# mLRS-dualE28-board02-v010.net
KiCad netlist of a schematic drawn in EAGLE
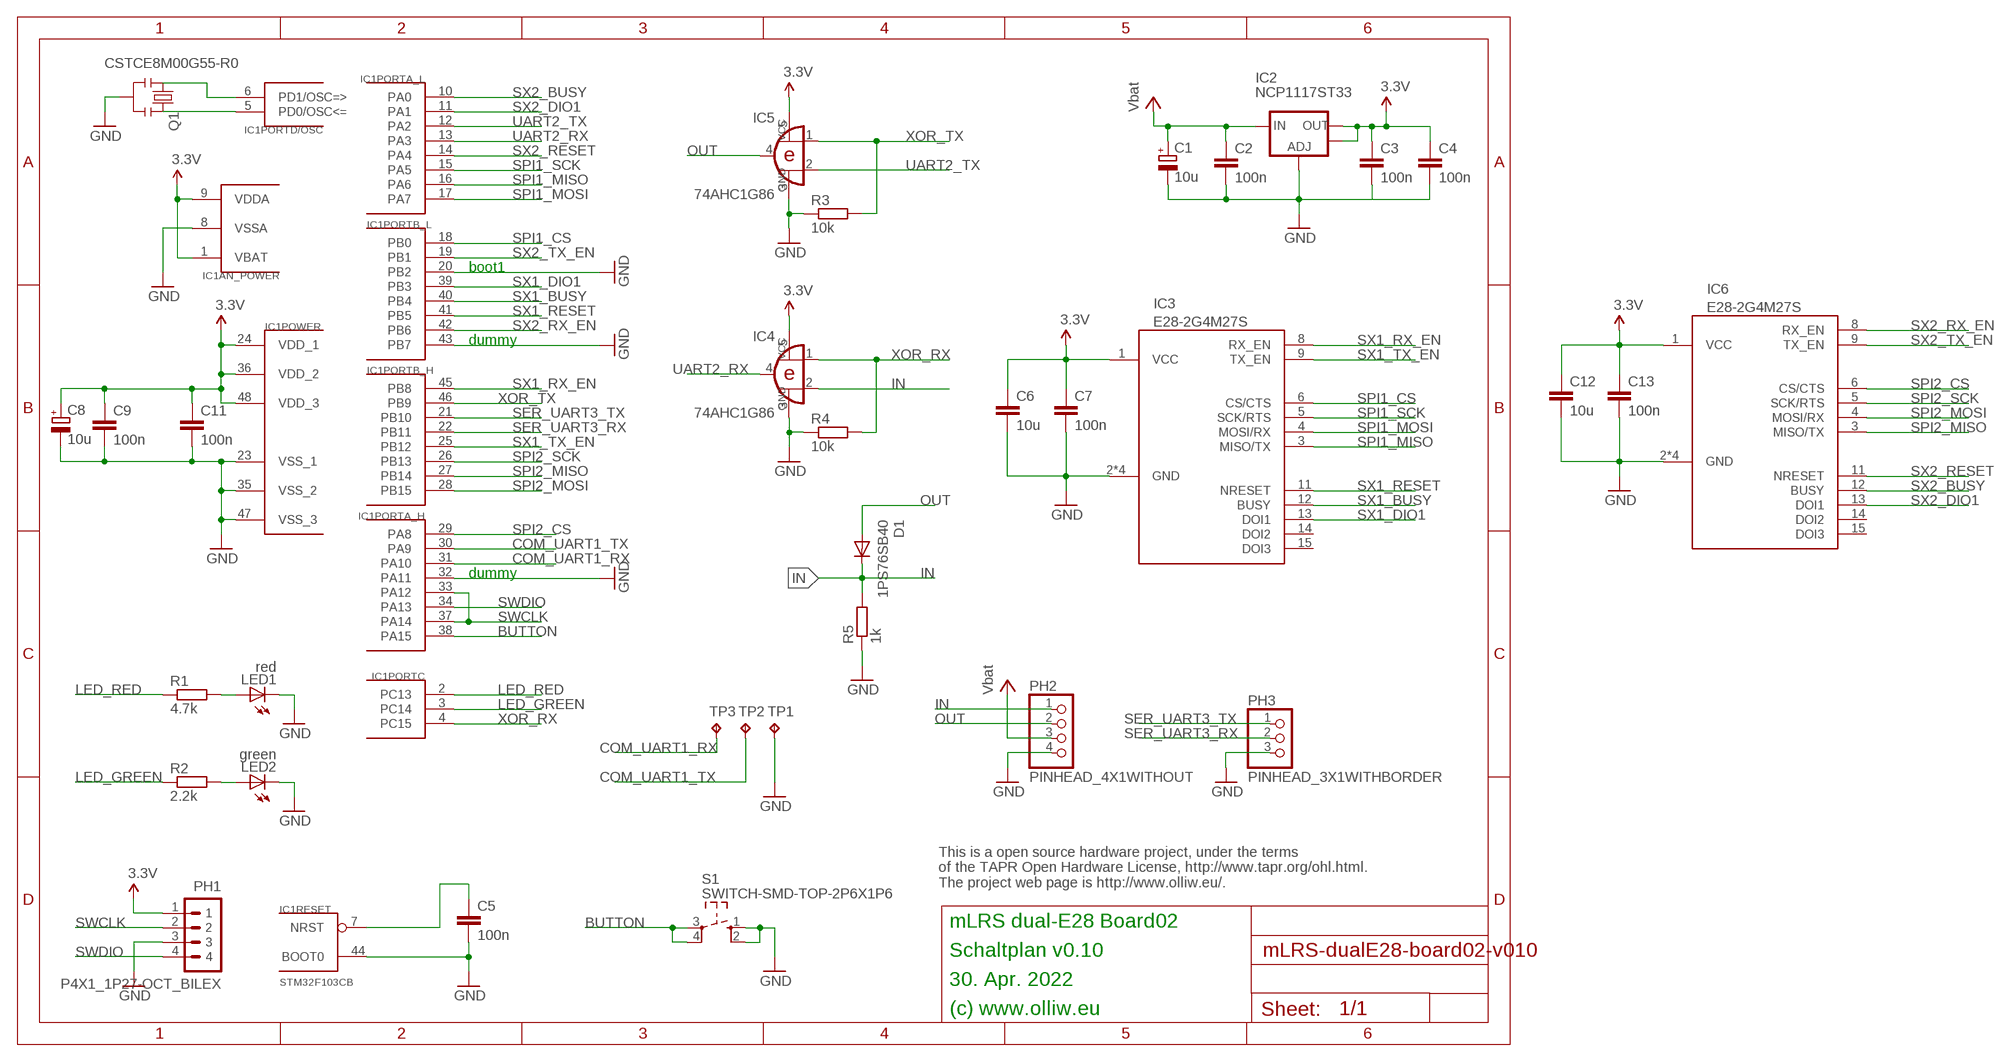
[diagram p0: schematic, sheet 1]

(export (version "E")
  (design (tool "Eeschema 10.0.6"))
  (components
    (comp (ref "C1")
      (value "10u")
      (footprint "eagle-import:SMC_A")
      (libsource (lib "eagle-import") (part "CPOL-EUSMCA"))
    )
    (comp (ref "C2")
      (value "100n")
      (footprint "eagle-import:C0603")
      (libsource (lib "eagle-import") (part "C-EUC0603"))
    )
    (comp (ref "C3")
      (value "100n")
      (footprint "eagle-import:C0402")
      (libsource (lib "eagle-import") (part "C-EUC0402"))
    )
    (comp (ref "C4")
      (value "100n")
      (footprint "eagle-import:C0402")
      (libsource (lib "eagle-import") (part "C-EUC0402"))
    )
    (comp (ref "C5")
      (value "100n")
      (footprint "eagle-import:C0402")
      (libsource (lib "eagle-import") (part "C-EUC0402"))
    )
    (comp (ref "C6")
      (value "10u")
      (footprint "eagle-import:C0603")
      (libsource (lib "eagle-import") (part "C-EUC0603"))
    )
    (comp (ref "C7")
      (value "100n")
      (footprint "eagle-import:C0402")
      (libsource (lib "eagle-import") (part "C-EUC0402"))
    )
    (comp (ref "C8")
      (value "10u")
      (footprint "eagle-import:SMC_A")
      (libsource (lib "eagle-import") (part "CPOL-EUSMCA"))
    )
    (comp (ref "C9")
      (value "100n")
      (footprint "eagle-import:C0402")
      (libsource (lib "eagle-import") (part "C-EUC0402"))
    )
    (comp (ref "C11")
      (value "100n")
      (footprint "eagle-import:C0402")
      (libsource (lib "eagle-import") (part "C-EUC0402"))
    )
    (comp (ref "C12")
      (value "10u")
      (footprint "eagle-import:C0603")
      (libsource (lib "eagle-import") (part "C-EUC0603"))
    )
    (comp (ref "C13")
      (value "100n")
      (footprint "eagle-import:C0402")
      (libsource (lib "eagle-import") (part "C-EUC0402"))
    )
    (comp (ref "D1")
      (value "1PS76SB40")
      (footprint "eagle-import:SOD110-R")
      (libsource (lib "eagle-import") (part "DIODE-SOD110-R"))
    )
    (comp (ref "IC1")
      (value "STM32F103CB")
      (footprint "eagle-import:TQFP48")
      (libsource (lib "eagle-import") (part "STM32F10XCXT6"))
    )
    (comp (ref "IC2")
      (value "NCP1117ST33")
      (footprint "eagle-import:SOT223")
      (libsource (lib "eagle-import") (part "V_REG_LM1117SOT223"))
    )
    (comp (ref "IC3")
      (value "E28-2G4M27S")
      (footprint "eagle-import:E28-2G4M27")
      (libsource (lib "eagle-import") (part "E28"))
    )
    (comp (ref "IC4")
      (value "74AHC1G86")
      (footprint "eagle-import:SOT23-5-VER1")
      (libsource (lib "eagle-import") (part "74AHC1G86"))
    )
    (comp (ref "IC5")
      (value "74AHC1G86")
      (footprint "eagle-import:SOT23-5-VER1")
      (libsource (lib "eagle-import") (part "74AHC1G86"))
    )
    (comp (ref "IC6")
      (value "E28-2G4M27S")
      (footprint "eagle-import:E28-2G4M27")
      (libsource (lib "eagle-import") (part "E28"))
    )
    (comp (ref "LED1")
      (value "red")
      (footprint "eagle-import:CHIPLED_0603")
      (libsource (lib "eagle-import") (part "LEDCHIPLED_0603"))
    )
    (comp (ref "LED2")
      (value "green")
      (footprint "eagle-import:CHIPLED_0603")
      (libsource (lib "eagle-import") (part "LEDCHIPLED_0603"))
    )
    (comp (ref "PH1")
      (value "P4X1_1P27-OCT_BILEX")
      (footprint "eagle-import:4X1_1P27_OCT_BILEX")
      (libsource (lib "eagle-import") (part "P4X1_1P27-OCT_BILEX"))
    )
    (comp (ref "PH2")
      (value "PINHEAD_4X1WITHOUT")
      (footprint "eagle-import:PINHEAD_4X1_WO")
      (libsource (lib "eagle-import") (part "PINHEAD_4X1WITHOUT"))
    )
    (comp (ref "PH3")
      (value "PINHEAD_3X1WITHBORDER")
      (footprint "eagle-import:PINHEAD_3X1")
      (libsource (lib "eagle-import") (part "PINHEAD_3X1WITHBORDER"))
    )
    (comp (ref "Q1")
      (value "CSTCE8M00G55-R0")
      (footprint "eagle-import:RESONATOR-SMD")
      (libsource (lib "eagle-import") (part "RESONATORSMD"))
    )
    (comp (ref "R1")
      (value "4.7k")
      (footprint "eagle-import:R0402")
      (libsource (lib "eagle-import") (part "R-EU_R0402"))
    )
    (comp (ref "R2")
      (value "2.2k")
      (footprint "eagle-import:R0402")
      (libsource (lib "eagle-import") (part "R-EU_R0402"))
    )
    (comp (ref "R3")
      (value "10k")
      (footprint "eagle-import:R0402")
      (libsource (lib "eagle-import") (part "R-EU_R0402"))
    )
    (comp (ref "R4")
      (value "10k")
      (footprint "eagle-import:R0402")
      (libsource (lib "eagle-import") (part "R-EU_R0402"))
    )
    (comp (ref "R5")
      (value "1k")
      (footprint "eagle-import:R0402")
      (libsource (lib "eagle-import") (part "R-EU_R0402"))
    )
    (comp (ref "S1")
      (value "SWITCH-SMD-TOP-2P6X1P6")
      (footprint "eagle-import:TACTILE-SWITCH-SMD-TOP-2P6X1X6")
      (libsource (lib "eagle-import") (part "SWITCH-SMD-TOP-2P6X1P6"))
    )
    (comp (ref "TP1")
      (value "TPB1,27")
      (footprint "eagle-import:B1,27")
      (libsource (lib "eagle-import") (part "TPB1,27"))
    )
    (comp (ref "TP2")
      (value "TPB1,27")
      (footprint "eagle-import:B1,27")
      (libsource (lib "eagle-import") (part "TPB1,27"))
    )
    (comp (ref "TP3")
      (value "TPB1,27")
      (footprint "eagle-import:B1,27")
      (libsource (lib "eagle-import") (part "TPB1,27"))
    )
  )
  (nets
    (net (code "1") (name "/BUTTON") (class "Default")
      (node (ref "IC1") (pin "38") (pinfunction "PA15_38") (pintype "bidirectional"))
      (node (ref "S1") (pin "3") (pinfunction "3_3") (pintype "passive"))
      (node (ref "S1") (pin "4") (pinfunction "4_4") (pintype "passive"))
    )
    (net (code "2") (name "/COM_UART1_RX") (class "Default")
      (node (ref "IC1") (pin "31") (pinfunction "PA10_31") (pintype "bidirectional"))
      (node (ref "TP3") (pin "TP") (pinfunction "TP_TP") (pintype "input"))
    )
    (net (code "3") (name "/COM_UART1_TX") (class "Default")
      (node (ref "IC1") (pin "30") (pinfunction "PA9_30") (pintype "bidirectional"))
      (node (ref "TP2") (pin "TP") (pinfunction "TP_TP") (pintype "input"))
    )
    (net (code "4") (name "/LED_GREEN") (class "Default")
      (node (ref "IC1") (pin "3") (pinfunction "PC14_3") (pintype "bidirectional"))
      (node (ref "R2") (pin "1") (pinfunction "1_1") (pintype "passive"))
    )
    (net (code "5") (name "/LED_RED") (class "Default")
      (node (ref "IC1") (pin "2") (pinfunction "PC13_2") (pintype "bidirectional"))
      (node (ref "R1") (pin "1") (pinfunction "1_1") (pintype "passive"))
    )
    (net (code "6") (name "/OUT") (class "Default")
      (node (ref "D1") (pin "A") (pinfunction "A_A") (pintype "passive"))
      (node (ref "IC5") (pin "4") (pinfunction "O_4") (pintype "output"))
      (node (ref "PH2") (pin "2") (pinfunction "2_2") (pintype "passive"))
    )
    (net (code "7") (name "/SER_UART3_RX") (class "Default")
      (node (ref "IC1") (pin "22") (pinfunction "PB11_22") (pintype "bidirectional"))
      (node (ref "PH3") (pin "2") (pinfunction "3_2") (pintype "passive"))
    )
    (net (code "8") (name "/SER_UART3_TX") (class "Default")
      (node (ref "IC1") (pin "21") (pinfunction "PB10_21") (pintype "bidirectional"))
      (node (ref "PH3") (pin "1") (pinfunction "1_1") (pintype "passive"))
    )
    (net (code "9") (name "/SPI1_CS") (class "Default")
      (node (ref "IC1") (pin "18") (pinfunction "PB0_18") (pintype "bidirectional"))
      (node (ref "IC3") (pin "6") (pinfunction "CS/CTS_6") (pintype "bidirectional"))
    )
    (net (code "10") (name "/SPI1_MISO") (class "Default")
      (node (ref "IC1") (pin "16") (pinfunction "PA6_16") (pintype "bidirectional"))
      (node (ref "IC3") (pin "3") (pinfunction "MISO/TX_3") (pintype "bidirectional"))
    )
    (net (code "11") (name "/SPI1_MOSI") (class "Default")
      (node (ref "IC1") (pin "17") (pinfunction "PA7_17") (pintype "bidirectional"))
      (node (ref "IC3") (pin "4") (pinfunction "MOSI/RX_4") (pintype "bidirectional"))
    )
    (net (code "12") (name "/SPI1_SCK") (class "Default")
      (node (ref "IC1") (pin "15") (pinfunction "PA5_15") (pintype "bidirectional"))
      (node (ref "IC3") (pin "5") (pinfunction "SCK/RTS_5") (pintype "bidirectional"))
    )
    (net (code "13") (name "/SPI2_CS") (class "Default")
      (node (ref "IC1") (pin "29") (pinfunction "PA8_29") (pintype "bidirectional"))
      (node (ref "IC6") (pin "6") (pinfunction "CS/CTS_6") (pintype "bidirectional"))
    )
    (net (code "14") (name "/SPI2_MISO") (class "Default")
      (node (ref "IC1") (pin "27") (pinfunction "PB14_27") (pintype "bidirectional"))
      (node (ref "IC6") (pin "3") (pinfunction "MISO/TX_3") (pintype "bidirectional"))
    )
    (net (code "15") (name "/SPI2_MOSI") (class "Default")
      (node (ref "IC1") (pin "28") (pinfunction "PB15_28") (pintype "bidirectional"))
      (node (ref "IC6") (pin "4") (pinfunction "MOSI/RX_4") (pintype "bidirectional"))
    )
    (net (code "16") (name "/SPI2_SCK") (class "Default")
      (node (ref "IC1") (pin "26") (pinfunction "PB13_26") (pintype "bidirectional"))
      (node (ref "IC6") (pin "5") (pinfunction "SCK/RTS_5") (pintype "bidirectional"))
    )
    (net (code "17") (name "/SWCLK") (class "Default")
      (node (ref "IC1") (pin "33") (pinfunction "PA12_33") (pintype "bidirectional"))
      (node (ref "IC1") (pin "37") (pinfunction "PA14_37") (pintype "bidirectional"))
      (node (ref "PH1") (pin "2") (pinfunction "2_2") (pintype "passive"))
    )
    (net (code "18") (name "/SWDIO") (class "Default")
      (node (ref "IC1") (pin "34") (pinfunction "PA13_34") (pintype "bidirectional"))
      (node (ref "PH1") (pin "4") (pinfunction "4_4") (pintype "passive"))
    )
    (net (code "19") (name "/SX1_BUSY") (class "Default")
      (node (ref "IC1") (pin "40") (pinfunction "PB4_40") (pintype "bidirectional"))
      (node (ref "IC3") (pin "12") (pinfunction "BUSY_12") (pintype "bidirectional"))
    )
    (net (code "20") (name "/SX1_DIO1") (class "Default")
      (node (ref "IC1") (pin "39") (pinfunction "PB3_39") (pintype "bidirectional"))
      (node (ref "IC3") (pin "13") (pinfunction "DOI1_13") (pintype "bidirectional"))
    )
    (net (code "21") (name "/SX1_RESET") (class "Default")
      (node (ref "IC1") (pin "41") (pinfunction "PB5_41") (pintype "bidirectional"))
      (node (ref "IC3") (pin "11") (pinfunction "NRESET_11") (pintype "input"))
    )
    (net (code "22") (name "/SX1_RX_EN") (class "Default")
      (node (ref "IC1") (pin "45") (pinfunction "PB8_45") (pintype "bidirectional"))
      (node (ref "IC3") (pin "8") (pinfunction "RX_EN_8") (pintype "bidirectional"))
    )
    (net (code "23") (name "/SX1_TX_EN") (class "Default")
      (node (ref "IC1") (pin "25") (pinfunction "PB12_25") (pintype "bidirectional"))
      (node (ref "IC3") (pin "9") (pinfunction "TX_EN_9") (pintype "bidirectional"))
    )
    (net (code "24") (name "/SX2_BUSY") (class "Default")
      (node (ref "IC1") (pin "10") (pinfunction "PA0_10") (pintype "bidirectional"))
      (node (ref "IC6") (pin "12") (pinfunction "BUSY_12") (pintype "bidirectional"))
    )
    (net (code "25") (name "/SX2_DIO1") (class "Default")
      (node (ref "IC1") (pin "11") (pinfunction "PA1_11") (pintype "bidirectional"))
      (node (ref "IC6") (pin "13") (pinfunction "DOI1_13") (pintype "bidirectional"))
    )
    (net (code "26") (name "/SX2_RESET") (class "Default")
      (node (ref "IC1") (pin "14") (pinfunction "PA4_14") (pintype "bidirectional"))
      (node (ref "IC6") (pin "11") (pinfunction "NRESET_11") (pintype "input"))
    )
    (net (code "27") (name "/SX2_RX_EN") (class "Default")
      (node (ref "IC1") (pin "42") (pinfunction "PB6_42") (pintype "bidirectional"))
      (node (ref "IC6") (pin "8") (pinfunction "RX_EN_8") (pintype "bidirectional"))
    )
    (net (code "28") (name "/SX2_TX_EN") (class "Default")
      (node (ref "IC1") (pin "19") (pinfunction "PB1_19") (pintype "bidirectional"))
      (node (ref "IC6") (pin "9") (pinfunction "TX_EN_9") (pintype "bidirectional"))
    )
    (net (code "29") (name "/UART2_RX") (class "Default")
      (node (ref "IC1") (pin "13") (pinfunction "PA3_13") (pintype "bidirectional"))
      (node (ref "IC4") (pin "4") (pinfunction "O_4") (pintype "output"))
    )
    (net (code "30") (name "/UART2_TX") (class "Default")
      (node (ref "IC1") (pin "12") (pinfunction "PA2_12") (pintype "bidirectional"))
      (node (ref "IC5") (pin "2") (pinfunction "I1_2") (pintype "input"))
    )
    (net (code "31") (name "/XOR_RX") (class "Default")
      (node (ref "IC1") (pin "4") (pinfunction "PC15_4") (pintype "bidirectional"))
      (node (ref "IC4") (pin "1") (pinfunction "I0_1") (pintype "input"))
      (node (ref "R4") (pin "2") (pinfunction "2_2") (pintype "passive"))
    )
    (net (code "32") (name "/XOR_TX") (class "Default")
      (node (ref "IC1") (pin "46") (pinfunction "PB9_46") (pintype "bidirectional"))
      (node (ref "IC5") (pin "1") (pinfunction "I0_1") (pintype "input"))
      (node (ref "R3") (pin "2") (pinfunction "2_2") (pintype "passive"))
    )
    (net (code "33") (name "3.3V") (class "Default")
      (node (ref "C11") (pin "1") (pinfunction "1_1") (pintype "passive"))
      (node (ref "C12") (pin "1") (pinfunction "1_1") (pintype "passive"))
      (node (ref "C13") (pin "1") (pinfunction "1_1") (pintype "passive"))
      (node (ref "C3") (pin "1") (pinfunction "1_1") (pintype "passive"))
      (node (ref "C4") (pin "1") (pinfunction "1_1") (pintype "passive"))
      (node (ref "C6") (pin "1") (pinfunction "1_1") (pintype "passive"))
      (node (ref "C7") (pin "1") (pinfunction "1_1") (pintype "passive"))
      (node (ref "C8") (pin "+") (pinfunction "+_+") (pintype "passive"))
      (node (ref "C9") (pin "1") (pinfunction "1_1") (pintype "passive"))
      (node (ref "IC1") (pin "1") (pinfunction "VBAT_1") (pintype "power_in"))
      (node (ref "IC1") (pin "24") (pinfunction "VDD_1_24") (pintype "power_in"))
      (node (ref "IC1") (pin "36") (pinfunction "VDD_2_36") (pintype "power_in"))
      (node (ref "IC1") (pin "48") (pinfunction "VDD_3_48") (pintype "power_in"))
      (node (ref "IC1") (pin "9") (pinfunction "VDDA_9") (pintype "power_in"))
      (node (ref "IC2") (pin "2") (pinfunction "OUT_2") (pintype "output"))
      (node (ref "IC2") (pin "4") (pinfunction "OUT_4") (pintype "output"))
      (node (ref "IC3") (pin "1") (pinfunction "VCC_1") (pintype "power_in"))
      (node (ref "IC4") (pin "5") (pinfunction "VCC_5") (pintype "power_in"))
      (node (ref "IC5") (pin "5") (pinfunction "VCC_5") (pintype "power_in"))
      (node (ref "IC6") (pin "1") (pinfunction "VCC_1") (pintype "power_in"))
      (node (ref "PH1") (pin "1") (pinfunction "1_1") (pintype "passive"))
    )
    (net (code "34") (name "GND") (class "Default")
      (node (ref "C1") (pin "-") (pinfunction "-_-") (pintype "passive"))
      (node (ref "C11") (pin "2") (pinfunction "2_2") (pintype "passive"))
      (node (ref "C12") (pin "2") (pinfunction "2_2") (pintype "passive"))
      (node (ref "C13") (pin "2") (pinfunction "2_2") (pintype "passive"))
      (node (ref "C2") (pin "2") (pinfunction "2_2") (pintype "passive"))
      (node (ref "C3") (pin "2") (pinfunction "2_2") (pintype "passive"))
      (node (ref "C4") (pin "2") (pinfunction "2_2") (pintype "passive"))
      (node (ref "C5") (pin "2") (pinfunction "2_2") (pintype "passive"))
      (node (ref "C6") (pin "2") (pinfunction "2_2") (pintype "passive"))
      (node (ref "C7") (pin "2") (pinfunction "2_2") (pintype "passive"))
      (node (ref "C8") (pin "-") (pinfunction "-_-") (pintype "passive"))
      (node (ref "C9") (pin "2") (pinfunction "2_2") (pintype "passive"))
      (node (ref "IC1") (pin "20") (pinfunction "PB2_20") (pintype "bidirectional"))
      (node (ref "IC1") (pin "23") (pinfunction "VSS_1_23") (pintype "power_in"))
      (node (ref "IC1") (pin "32") (pinfunction "PA11_32") (pintype "bidirectional"))
      (node (ref "IC1") (pin "35") (pinfunction "VSS_2_35") (pintype "power_in"))
      (node (ref "IC1") (pin "43") (pinfunction "PB7_43") (pintype "bidirectional"))
      (node (ref "IC1") (pin "44") (pinfunction "BOOT0_44") (pintype "input"))
      (node (ref "IC1") (pin "47") (pinfunction "VSS_3_47") (pintype "power_in"))
      (node (ref "IC1") (pin "8") (pinfunction "VSSA_8") (pintype "power_in"))
      (node (ref "IC2") (pin "1") (pinfunction "ADJ_1") (pintype "input"))
      (node (ref "IC3") (pin "10") (pinfunction "GND_10") (pintype "power_in"))
      (node (ref "IC3") (pin "16") (pinfunction "GND_16") (pintype "power_in"))
      (node (ref "IC3") (pin "2") (pinfunction "GND_2") (pintype "power_in"))
      (node (ref "IC3") (pin "7") (pinfunction "GND_7") (pintype "power_in"))
      (node (ref "IC4") (pin "3") (pinfunction "GND_3") (pintype "power_in"))
      (node (ref "IC5") (pin "3") (pinfunction "GND_3") (pintype "power_in"))
      (node (ref "IC6") (pin "10") (pinfunction "GND_10") (pintype "power_in"))
      (node (ref "IC6") (pin "16") (pinfunction "GND_16") (pintype "power_in"))
      (node (ref "IC6") (pin "2") (pinfunction "GND_2") (pintype "power_in"))
      (node (ref "IC6") (pin "7") (pinfunction "GND_7") (pintype "power_in"))
      (node (ref "LED1") (pin "C") (pinfunction "C_C") (pintype "passive"))
      (node (ref "LED2") (pin "C") (pinfunction "C_C") (pintype "passive"))
      (node (ref "PH1") (pin "3") (pinfunction "3_3") (pintype "passive"))
      (node (ref "PH2") (pin "4") (pinfunction "4_4") (pintype "passive"))
      (node (ref "PH3") (pin "3") (pinfunction "5_3") (pintype "passive"))
      (node (ref "Q1") (pin "2") (pinfunction "2_2") (pintype "passive"))
      (node (ref "R3") (pin "1") (pinfunction "1_1") (pintype "passive"))
      (node (ref "R4") (pin "1") (pinfunction "1_1") (pintype "passive"))
      (node (ref "R5") (pin "1") (pinfunction "1_1") (pintype "passive"))
      (node (ref "S1") (pin "1") (pinfunction "1_1") (pintype "passive"))
      (node (ref "S1") (pin "2") (pinfunction "2_2") (pintype "passive"))
      (node (ref "TP1") (pin "TP") (pinfunction "TP_TP") (pintype "input"))
    )
    (net (code "35") (name "IN") (class "Default")
      (node (ref "D1") (pin "C") (pinfunction "C_C") (pintype "passive"))
      (node (ref "IC4") (pin "2") (pinfunction "I1_2") (pintype "input"))
      (node (ref "PH2") (pin "1") (pinfunction "1_1") (pintype "passive"))
      (node (ref "R5") (pin "2") (pinfunction "2_2") (pintype "passive"))
    )
    (net (code "36") (name "Net-(IC1G-PD0{slash}OSC<=)") (class "Default")
      (node (ref "IC1") (pin "5") (pinfunction "PD0/OSC<=_5") (pintype "bidirectional"))
      (node (ref "Q1") (pin "3") (pinfunction "3_3") (pintype "passive"))
    )
    (net (code "37") (name "Net-(IC1G-PD1{slash}OSC=>)") (class "Default")
      (node (ref "IC1") (pin "6") (pinfunction "PD1/OSC=>_6") (pintype "bidirectional"))
      (node (ref "Q1") (pin "1") (pinfunction "1_1") (pintype "passive"))
    )
    (net (code "38") (name "Net-(IC1I-NRST)") (class "Default")
      (node (ref "C5") (pin "1") (pinfunction "1_1") (pintype "passive"))
      (node (ref "IC1") (pin "7") (pinfunction "NRST_7") (pintype "input"))
    )
    (net (code "39") (name "Net-(LED1-PadA)") (class "Default")
      (node (ref "LED1") (pin "A") (pinfunction "A_A") (pintype "passive"))
      (node (ref "R1") (pin "2") (pinfunction "2_2") (pintype "passive"))
    )
    (net (code "40") (name "Net-(LED2-PadA)") (class "Default")
      (node (ref "LED2") (pin "A") (pinfunction "A_A") (pintype "passive"))
      (node (ref "R2") (pin "2") (pinfunction "2_2") (pintype "passive"))
    )
    (net (code "41") (name "Vbat") (class "Default")
      (node (ref "C1") (pin "+") (pinfunction "+_+") (pintype "passive"))
      (node (ref "C2") (pin "1") (pinfunction "1_1") (pintype "passive"))
      (node (ref "IC2") (pin "3") (pinfunction "IN_3") (pintype "input"))
      (node (ref "PH2") (pin "3") (pinfunction "3_3") (pintype "passive"))
    )
    (net (code "42") (name "unconnected-(IC3-DOI2-Pad14)") (class "Default")
      (node (ref "IC3") (pin "14") (pinfunction "DOI2_14") (pintype "bidirectional"))
    )
    (net (code "43") (name "unconnected-(IC3-DOI3-Pad15)") (class "Default")
      (node (ref "IC3") (pin "15") (pinfunction "DOI3_15") (pintype "bidirectional"))
    )
    (net (code "44") (name "unconnected-(IC6-DOI2-Pad14)") (class "Default")
      (node (ref "IC6") (pin "14") (pinfunction "DOI2_14") (pintype "bidirectional"))
    )
    (net (code "45") (name "unconnected-(IC6-DOI3-Pad15)") (class "Default")
      (node (ref "IC6") (pin "15") (pinfunction "DOI3_15") (pintype "bidirectional"))
    )
  )
)
